# STM32_CORE.net
KiCad netlist of a schematic drawn in Altium Designer
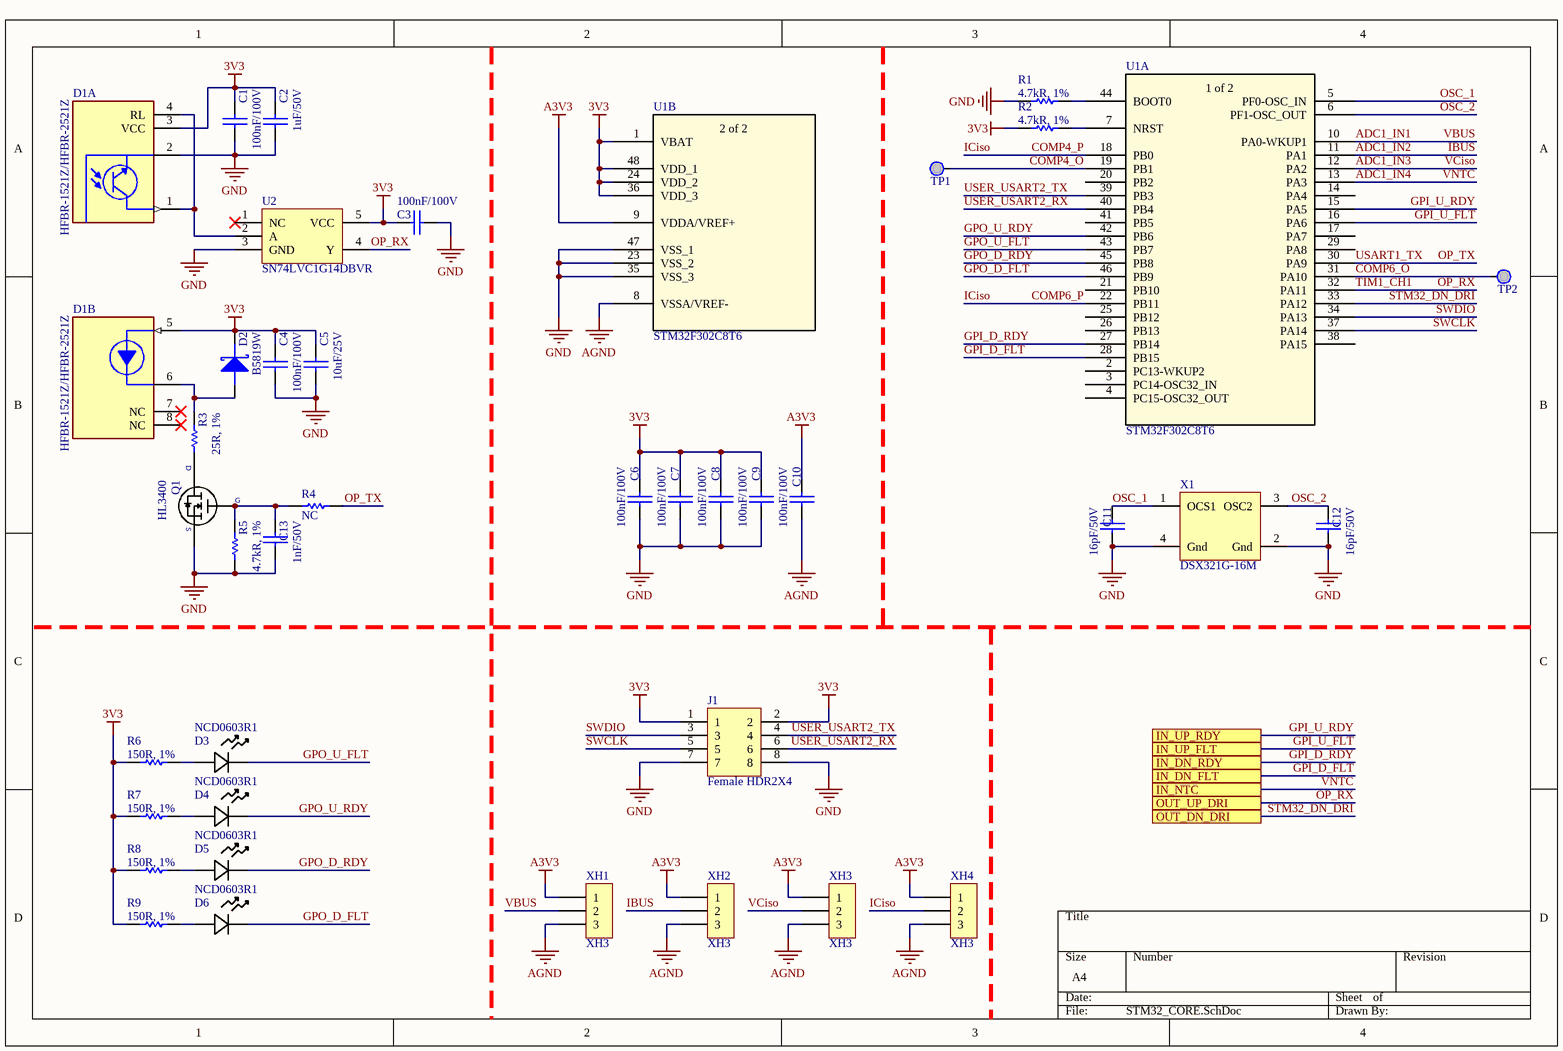
[diagram p0: STM32_CORE.SchDoc]

(export (version "E")
  (design (tool "Eeschema 10.0.6"))
  (components
    (comp (ref "C1")
      (value "100nF/100V")
      (footprint "0603C")
      (description "CC0603KRX7R9BB104")
      (libsource (lib "MyLib") (part "CAP"))
    )
    (comp (ref "C2")
      (value "1uF/50V")
      (footprint "0603C")
      (description "CC0603KRX7R9BB105")
      (libsource (lib "MyLib") (part "CAP"))
    )
    (comp (ref "C3")
      (value "100nF/100V")
      (footprint "0603C")
      (description "CC0603KRX7R9BB104")
      (libsource (lib "MyLib") (part "CAP"))
    )
    (comp (ref "C4")
      (value "100nF/100V")
      (footprint "0603C")
      (description "CC0603KRX7R9BB104")
      (libsource (lib "MyLib") (part "CAP"))
    )
    (comp (ref "C5")
      (value "10uF/25V")
      (footprint "0603C")
      (description "CC0603MRX5R8BB106")
      (libsource (lib "MyLib") (part "CAP"))
    )
    (comp (ref "C6")
      (value "100nF/100V")
      (footprint "0603C")
      (description "CC0603KRX7R9BB104")
      (libsource (lib "MyLib") (part "CAP"))
    )
    (comp (ref "C7")
      (value "100nF/100V")
      (footprint "0603C")
      (description "CC0603KRX7R9BB104")
      (libsource (lib "MyLib") (part "CAP"))
    )
    (comp (ref "C8")
      (value "100nF/100V")
      (footprint "0603C")
      (description "CC0603KRX7R9BB104")
      (libsource (lib "MyLib") (part "CAP"))
    )
    (comp (ref "C9")
      (value "100nF/100V")
      (footprint "0603C")
      (description "CC0603KRX7R9BB104")
      (libsource (lib "MyLib") (part "CAP"))
    )
    (comp (ref "C10")
      (value "100nF/100V")
      (footprint "0603C")
      (description "CC0603KRX7R9BB104")
      (libsource (lib "MyLib") (part "CAP"))
    )
    (comp (ref "C11")
      (value "16pF/50V")
      (footprint "0603C")
      (description "CC0603FRNPO9BN160")
      (libsource (lib "MyLib") (part "CAP"))
    )
    (comp (ref "C12")
      (value "16pF/50V")
      (footprint "0603C")
      (description "CC0603FRNPO9BN160")
      (libsource (lib "MyLib") (part "CAP"))
    )
    (comp (ref "C13")
      (value "1nF/50V")
      (footprint "0603C")
      (description "CC0603KRX7R9BB102")
      (libsource (lib "MyLib") (part "CAP"))
    )
    (comp (ref "D1")
      (value "HFBR-1521Z/HFBR-2521Z")
      (footprint "HFBR_XX21Z_UNION")
      (description "Versatile Link Fiber-Optic Connection")
      (libsource (lib "CustomizedLib") (part "HFBR_XX21Z_UNION"))
    )
    (comp (ref "D2") (value "B5819W") (footprint "SOD-123") (libsource (lib "MyLib") (part "DIODE SCHOTTKY")))
    (comp (ref "D3")
      (value "NCD0603R1")
      (footprint "LED_LSQ976_OSR")
      (description "No Description Available")
      (fields
        (field (name "MANUFACTURER_PART_NUMBER") "LSQ976")
        (field (name "COPYRIGHT") "Copyright (C) 2025 Ultra Librarian. All rights reserved.")
      )
      (libsource (lib "CustomizedLib") (part "LED"))
    )
    (comp (ref "D4")
      (value "NCD0603R1")
      (footprint "LED_LSQ976_OSR")
      (description "No Description Available")
      (fields
        (field (name "MANUFACTURER_PART_NUMBER") "LSQ976")
        (field (name "COPYRIGHT") "Copyright (C) 2025 Ultra Librarian. All rights reserved.")
      )
      (libsource (lib "CustomizedLib") (part "LED"))
    )
    (comp (ref "D5")
      (value "NCD0603R1")
      (footprint "LED_LSQ976_OSR")
      (description "No Description Available")
      (fields
        (field (name "MANUFACTURER_PART_NUMBER") "LSQ976")
        (field (name "COPYRIGHT") "Copyright (C) 2025 Ultra Librarian. All rights reserved.")
      )
      (libsource (lib "CustomizedLib") (part "LED"))
    )
    (comp (ref "D6")
      (value "NCD0603R1")
      (footprint "LED_LSQ976_OSR")
      (description "No Description Available")
      (fields
        (field (name "MANUFACTURER_PART_NUMBER") "LSQ976")
        (field (name "COPYRIGHT") "Copyright (C) 2025 Ultra Librarian. All rights reserved.")
      )
      (libsource (lib "CustomizedLib") (part "LED"))
    )
    (comp (ref "J1")
      (value "Female HDR2X4")
      (footprint "Fe-HDR2X4/2.54-S")
      (libsource (lib "MyLib") (part "Female HDR2X4"))
    )
    (comp (ref "Q1") (value "HL3400") (footprint "SOT23-3") (libsource (lib "CustomizedLib") (part "NMOS")))
    (comp (ref "R1")
      (value "4.7kR, 1%")
      (footprint "0603R")
      (description "RC0603FR-074K7L")
      (libsource (lib "MyLib") (part "RES"))
    )
    (comp (ref "R2")
      (value "4.7kR, 1%")
      (footprint "0603R")
      (description "RC0603FR-074K7L")
      (libsource (lib "MyLib") (part "RES"))
    )
    (comp (ref "R3")
      (value "25R, 1%")
      (footprint "0603R")
      (description "RP0603BRD0725RL")
      (libsource (lib "MyLib") (part "RES"))
    )
    (comp (ref "R4") (value "NC") (footprint "0603R") (libsource (lib "MyLib") (part "RES")))
    (comp (ref "R5")
      (value "4.7kR, 1%")
      (footprint "0603R")
      (description "RC0603FR-074K7L")
      (libsource (lib "MyLib") (part "RES"))
    )
    (comp (ref "R6")
      (value "150R, 1%")
      (footprint "0603R")
      (description "RC0603FR-07150RL")
      (libsource (lib "MyLib") (part "RES"))
    )
    (comp (ref "R7")
      (value "150R, 1%")
      (footprint "0603R")
      (description "RC0603FR-07150RL")
      (libsource (lib "MyLib") (part "RES"))
    )
    (comp (ref "R8")
      (value "150R, 1%")
      (footprint "0603R")
      (description "RC0603FR-07150RL")
      (libsource (lib "MyLib") (part "RES"))
    )
    (comp (ref "R9")
      (value "150R, 1%")
      (footprint "0603R")
      (description "RC0603FR-07150RL")
      (libsource (lib "MyLib") (part "RES"))
    )
    (comp (ref "TP1") (value "Test Point") (footprint "TP") (libsource (lib "CustomizedLib") (part "TP")))
    (comp (ref "TP2") (value "Test Point") (footprint "TP") (libsource (lib "CustomizedLib") (part "TP")))
    (comp (ref "U1")
      (value "STM32F302C8T6")
      (footprint "LQFP48-7x7mm")
      (fields (field (name "COPYRIGHT") "Copyright (C) 2025 Ultra Librarian. All rights reserved."))
      (libsource (lib "CustomizedLib") (part "STM32F302C8T6"))
    )
    (comp (ref "U2")
      (value "SN74LVC1G14DBVR")
      (footprint "SOT23-5")
      (description "Y=A\\")
      (libsource (lib "CustomizedLib") (part "SN74LVC1G14DBVR"))
    )
    (comp (ref "X1")
      (value "DSX321G-16M")
      (footprint "SMD3225-4")
      (description "无源晶振")
      (libsource (lib "CustomizedLib") (part "DSX321G-16M"))
    )
    (comp (ref "XH1") (value "XH3") (footprint "XH3/2.54mm/180") (libsource (lib "MyLib") (part "XH3")))
    (comp (ref "XH2") (value "XH3") (footprint "XH3/2.54mm/180") (libsource (lib "MyLib") (part "XH3")))
    (comp (ref "XH3") (value "XH3") (footprint "XH3/2.54mm/180") (libsource (lib "MyLib") (part "XH3")))
    (comp (ref "XH4") (value "XH3") (footprint "XH3/2.54mm/180") (libsource (lib "MyLib") (part "XH3")))
  )
  (nets
    (net (code "1") (name "/ADC1_IN1") (class "Default")
      (node (ref "U1") (pin "10") (pinfunction "PA0-WKUP1_10") (pintype "passive"))
      (node (ref "XH1") (pin "2") (pinfunction "2_2") (pintype "passive"))
    )
    (net (code "2") (name "/ADC1_IN2") (class "Default")
      (node (ref "U1") (pin "11") (pinfunction "PA1_11") (pintype "passive"))
      (node (ref "XH2") (pin "2") (pinfunction "2_2") (pintype "passive"))
    )
    (net (code "3") (name "/ADC1_IN3") (class "Default")
      (node (ref "U1") (pin "12") (pinfunction "PA2_12") (pintype "passive"))
      (node (ref "XH3") (pin "2") (pinfunction "2_2") (pintype "passive"))
    )
    (net (code "4") (name "/ADC1_IN4") (class "Default")
      (node (ref "U1") (pin "13") (pinfunction "PA3_13") (pintype "passive"))
    )
    (net (code "5") (name "/COMP4_O") (class "Default")
      (node (ref "TP1") (pin "1") (pinfunction "1_1") (pintype "passive"))
      (node (ref "U1") (pin "19") (pinfunction "PB1_19") (pintype "passive"))
    )
    (net (code "6") (name "/COMP4_P") (class "Default")
      (node (ref "U1") (pin "18") (pinfunction "PB0_18") (pintype "passive"))
      (node (ref "U1") (pin "22") (pinfunction "PB11_22") (pintype "passive"))
      (node (ref "XH4") (pin "2") (pinfunction "2_2") (pintype "passive"))
    )
    (net (code "7") (name "/COMP6_O") (class "Default")
      (node (ref "TP2") (pin "1") (pinfunction "1_1") (pintype "passive"))
      (node (ref "U1") (pin "31") (pinfunction "PA10_31") (pintype "passive"))
    )
    (net (code "8") (name "/GPI_D_FLT") (class "Default")
      (node (ref "U1") (pin "28") (pinfunction "PB15_28") (pintype "passive"))
    )
    (net (code "9") (name "/GPI_D_RDY") (class "Default")
      (node (ref "U1") (pin "27") (pinfunction "PB14_27") (pintype "passive"))
    )
    (net (code "10") (name "/GPI_U_FLT") (class "Default")
      (node (ref "U1") (pin "16") (pinfunction "PA6_16") (pintype "passive"))
    )
    (net (code "11") (name "/GPI_U_RDY") (class "Default")
      (node (ref "U1") (pin "15") (pinfunction "PA5_15") (pintype "passive"))
    )
    (net (code "12") (name "/GPO_D_FLT") (class "Default")
      (node (ref "D6") (pin "1") (pinfunction "1_1") (pintype "passive"))
      (node (ref "U1") (pin "46") (pinfunction "PB9_46") (pintype "passive"))
    )
    (net (code "13") (name "/GPO_D_RDY") (class "Default")
      (node (ref "D5") (pin "1") (pinfunction "1_1") (pintype "passive"))
      (node (ref "U1") (pin "45") (pinfunction "PB8_45") (pintype "passive"))
    )
    (net (code "14") (name "/GPO_U_FLT") (class "Default")
      (node (ref "D3") (pin "1") (pinfunction "1_1") (pintype "passive"))
      (node (ref "U1") (pin "43") (pinfunction "PB7_43") (pintype "passive"))
    )
    (net (code "15") (name "/GPO_U_RDY") (class "Default")
      (node (ref "D4") (pin "1") (pinfunction "1_1") (pintype "passive"))
      (node (ref "U1") (pin "42") (pinfunction "PB6_42") (pintype "passive"))
    )
    (net (code "16") (name "/OP_RX") (class "Default")
      (node (ref "U1") (pin "32") (pinfunction "PA11_32") (pintype "passive"))
      (node (ref "U2") (pin "4") (pinfunction "Y_4") (pintype "passive"))
    )
    (net (code "17") (name "/OP_TX") (class "Default")
      (node (ref "R4") (pin "1") (pinfunction "1_1") (pintype "passive"))
      (node (ref "U1") (pin "30") (pinfunction "PA9_30") (pintype "passive"))
    )
    (net (code "18") (name "/OSC_1") (class "Default")
      (node (ref "C11") (pin "2") (pinfunction "2_2") (pintype "passive"))
      (node (ref "U1") (pin "5") (pinfunction "PF0-OSC_IN_5") (pintype "passive"))
      (node (ref "X1") (pin "1") (pinfunction "OCS1_1") (pintype "passive"))
    )
    (net (code "19") (name "/OSC_2") (class "Default")
      (node (ref "C12") (pin "1") (pinfunction "1_1") (pintype "passive"))
      (node (ref "U1") (pin "6") (pinfunction "PF1-OSC_OUT_6") (pintype "passive"))
      (node (ref "X1") (pin "3") (pinfunction "OSC2_3") (pintype "passive"))
    )
    (net (code "20") (name "/STM32_DN_DRI") (class "Default")
      (node (ref "U1") (pin "33") (pinfunction "PA12_33") (pintype "passive"))
    )
    (net (code "21") (name "/SWCLK") (class "Default")
      (node (ref "J1") (pin "5") (pinfunction "5_5") (pintype "passive"))
      (node (ref "U1") (pin "37") (pinfunction "PA14_37") (pintype "passive"))
    )
    (net (code "22") (name "/SWDIO") (class "Default")
      (node (ref "J1") (pin "3") (pinfunction "3_3") (pintype "passive"))
      (node (ref "U1") (pin "34") (pinfunction "PA13_34") (pintype "passive"))
    )
    (net (code "23") (name "/USER_USART2_RX") (class "Default")
      (node (ref "J1") (pin "6") (pinfunction "6_6") (pintype "passive"))
      (node (ref "U1") (pin "40") (pinfunction "PB4_40") (pintype "passive"))
    )
    (net (code "24") (name "/USER_USART2_TX") (class "Default")
      (node (ref "J1") (pin "4") (pinfunction "4_4") (pintype "passive"))
      (node (ref "U1") (pin "39") (pinfunction "PB3_39") (pintype "passive"))
    )
    (net (code "25") (name "3V3") (class "Default")
      (node (ref "C1") (pin "1") (pinfunction "1_1") (pintype "passive"))
      (node (ref "C2") (pin "2") (pinfunction "2_2") (pintype "passive"))
      (node (ref "C3") (pin "1") (pinfunction "1_1") (pintype "passive"))
      (node (ref "C4") (pin "1") (pinfunction "1_1") (pintype "passive"))
      (node (ref "C5") (pin "1") (pinfunction "1_1") (pintype "passive"))
      (node (ref "C6") (pin "1") (pinfunction "1_1") (pintype "passive"))
      (node (ref "C7") (pin "1") (pinfunction "1_1") (pintype "passive"))
      (node (ref "C8") (pin "1") (pinfunction "1_1") (pintype "passive"))
      (node (ref "C9") (pin "1") (pinfunction "1_1") (pintype "passive"))
      (node (ref "D1") (pin "3") (pinfunction "VCC_3") (pintype "power_in"))
      (node (ref "D1") (pin "5") (pinfunction "VO_5") (pintype "input"))
      (node (ref "D2") (pin "K") (pinfunction "K_K") (pintype "passive"))
      (node (ref "J1") (pin "1") (pinfunction "1_1") (pintype "passive"))
      (node (ref "J1") (pin "2") (pinfunction "2_2") (pintype "passive"))
      (node (ref "R2") (pin "1") (pinfunction "1_1") (pintype "passive"))
      (node (ref "R6") (pin "1") (pinfunction "1_1") (pintype "passive"))
      (node (ref "R7") (pin "1") (pinfunction "1_1") (pintype "passive"))
      (node (ref "R8") (pin "1") (pinfunction "1_1") (pintype "passive"))
      (node (ref "R9") (pin "1") (pinfunction "1_1") (pintype "passive"))
      (node (ref "U1") (pin "1") (pinfunction "VBAT_1") (pintype "power_in"))
      (node (ref "U1") (pin "24") (pinfunction "VDD_2_24") (pintype "power_in"))
      (node (ref "U1") (pin "36") (pinfunction "VDD_3_36") (pintype "power_in"))
      (node (ref "U1") (pin "48") (pinfunction "VDD_1_48") (pintype "power_in"))
      (node (ref "U2") (pin "5") (pinfunction "VCC_5") (pintype "passive"))
    )
    (net (code "26") (name "A3V3") (class "Default")
      (node (ref "C10") (pin "1") (pinfunction "1_1") (pintype "passive"))
      (node (ref "U1") (pin "9") (pinfunction "VDDA/VREF+_9") (pintype "power_in"))
      (node (ref "XH1") (pin "1") (pinfunction "1_1") (pintype "passive"))
      (node (ref "XH2") (pin "1") (pinfunction "1_1") (pintype "passive"))
      (node (ref "XH3") (pin "1") (pinfunction "1_1") (pintype "passive"))
      (node (ref "XH4") (pin "1") (pinfunction "1_1") (pintype "passive"))
    )
    (net (code "27") (name "AGND") (class "Default")
      (node (ref "C10") (pin "2") (pinfunction "2_2") (pintype "passive"))
      (node (ref "U1") (pin "8") (pinfunction "VSSA/VREF-_8") (pintype "power_in"))
      (node (ref "XH1") (pin "3") (pinfunction "3_3") (pintype "passive"))
      (node (ref "XH2") (pin "3") (pinfunction "3_3") (pintype "passive"))
      (node (ref "XH3") (pin "3") (pinfunction "3_3") (pintype "passive"))
      (node (ref "XH4") (pin "3") (pinfunction "3_3") (pintype "passive"))
    )
    (net (code "28") (name "GND") (class "Default")
      (node (ref "C1") (pin "2") (pinfunction "2_2") (pintype "passive"))
      (node (ref "C11") (pin "1") (pinfunction "1_1") (pintype "passive"))
      (node (ref "C12") (pin "2") (pinfunction "2_2") (pintype "passive"))
      (node (ref "C13") (pin "1") (pinfunction "1_1") (pintype "passive"))
      (node (ref "C2") (pin "1") (pinfunction "1_1") (pintype "passive"))
      (node (ref "C3") (pin "2") (pinfunction "2_2") (pintype "passive"))
      (node (ref "C4") (pin "2") (pinfunction "2_2") (pintype "passive"))
      (node (ref "C5") (pin "2") (pinfunction "2_2") (pintype "passive"))
      (node (ref "C6") (pin "2") (pinfunction "2_2") (pintype "passive"))
      (node (ref "C7") (pin "2") (pinfunction "2_2") (pintype "passive"))
      (node (ref "C8") (pin "2") (pinfunction "2_2") (pintype "passive"))
      (node (ref "C9") (pin "2") (pinfunction "2_2") (pintype "passive"))
      (node (ref "D1") (pin "2") (pinfunction "GROUND_2") (pintype "power_in"))
      (node (ref "J1") (pin "7") (pinfunction "7_7") (pintype "passive"))
      (node (ref "J1") (pin "8") (pinfunction "8_8") (pintype "passive"))
      (node (ref "Q1") (pin "2") (pinfunction "2_2") (pintype "passive"))
      (node (ref "R1") (pin "1") (pinfunction "1_1") (pintype "passive"))
      (node (ref "R5") (pin "1") (pinfunction "1_1") (pintype "passive"))
      (node (ref "U1") (pin "23") (pinfunction "VSS_2_23") (pintype "power_in"))
      (node (ref "U1") (pin "35") (pinfunction "VSS_3_35") (pintype "power_in"))
      (node (ref "U1") (pin "47") (pinfunction "VSS_1_47") (pintype "power_in"))
      (node (ref "U2") (pin "3") (pinfunction "GND_3") (pintype "passive"))
      (node (ref "X1") (pin "2") (pinfunction "Gnd_2") (pintype "passive"))
      (node (ref "X1") (pin "4") (pinfunction "Gnd_4") (pintype "passive"))
    )
    (net (code "29") (name "Net-(C13-Pad2)") (class "Default")
      (node (ref "C13") (pin "2") (pinfunction "2_2") (pintype "passive"))
      (node (ref "Q1") (pin "1") (pinfunction "1_1") (pintype "passive"))
      (node (ref "R4") (pin "2") (pinfunction "2_2") (pintype "passive"))
      (node (ref "R5") (pin "2") (pinfunction "2_2") (pintype "passive"))
    )
    (net (code "30") (name "Net-(D1A-RL)") (class "Default")
      (node (ref "D1") (pin "1") (pinfunction "VO_1") (pintype "output"))
      (node (ref "D1") (pin "4") (pinfunction "RL_4") (pintype "passive"))
      (node (ref "U2") (pin "2") (pinfunction "A_2") (pintype "passive"))
    )
    (net (code "31") (name "Net-(D1B-GROUND)") (class "Default")
      (node (ref "D1") (pin "6") (pinfunction "GROUND_6") (pintype "power_in"))
      (node (ref "D2") (pin "A") (pinfunction "A_A") (pintype "passive"))
      (node (ref "R3") (pin "1") (pinfunction "1_1") (pintype "passive"))
    )
    (net (code "32") (name "Net-(D3-Pad2)") (class "Default")
      (node (ref "D3") (pin "2") (pinfunction "2_2") (pintype "passive"))
      (node (ref "R6") (pin "2") (pinfunction "2_2") (pintype "passive"))
    )
    (net (code "33") (name "Net-(D4-Pad2)") (class "Default")
      (node (ref "D4") (pin "2") (pinfunction "2_2") (pintype "passive"))
      (node (ref "R7") (pin "2") (pinfunction "2_2") (pintype "passive"))
    )
    (net (code "34") (name "Net-(D5-Pad2)") (class "Default")
      (node (ref "D5") (pin "2") (pinfunction "2_2") (pintype "passive"))
      (node (ref "R8") (pin "2") (pinfunction "2_2") (pintype "passive"))
    )
    (net (code "35") (name "Net-(D6-Pad2)") (class "Default")
      (node (ref "D6") (pin "2") (pinfunction "2_2") (pintype "passive"))
      (node (ref "R9") (pin "2") (pinfunction "2_2") (pintype "passive"))
    )
    (net (code "36") (name "Net-(Q1-Pad3)") (class "Default")
      (node (ref "Q1") (pin "3") (pinfunction "3_3") (pintype "passive"))
      (node (ref "R3") (pin "2") (pinfunction "2_2") (pintype "passive"))
    )
    (net (code "37") (name "Net-(U1A-BOOT0)") (class "Default")
      (node (ref "R1") (pin "2") (pinfunction "2_2") (pintype "passive"))
      (node (ref "U1") (pin "44") (pinfunction "BOOT0_44") (pintype "passive"))
    )
    (net (code "38") (name "Net-(U1A-NRST)") (class "Default")
      (node (ref "R2") (pin "2") (pinfunction "2_2") (pintype "passive"))
      (node (ref "U1") (pin "7") (pinfunction "NRST_7") (pintype "passive"))
    )
    (net (code "39") (name "unconnected-(D1B-NC-Pad7)") (class "Default")
      (node (ref "D1") (pin "7") (pinfunction "NC_7") (pintype "passive+no_connect"))
    )
    (net (code "40") (name "unconnected-(D1B-NC-Pad8)") (class "Default")
      (node (ref "D1") (pin "8") (pinfunction "NC_8") (pintype "power_in+no_connect"))
    )
    (net (code "41") (name "unconnected-(U1A-PA4-Pad14)") (class "Default")
      (node (ref "U1") (pin "14") (pinfunction "PA4_14") (pintype "passive"))
    )
    (net (code "42") (name "unconnected-(U1A-PA7-Pad17)") (class "Default")
      (node (ref "U1") (pin "17") (pinfunction "PA7_17") (pintype "passive"))
    )
    (net (code "43") (name "unconnected-(U1A-PA8-Pad29)") (class "Default")
      (node (ref "U1") (pin "29") (pinfunction "PA8_29") (pintype "passive"))
    )
    (net (code "44") (name "unconnected-(U1A-PA15-Pad38)") (class "Default")
      (node (ref "U1") (pin "38") (pinfunction "PA15_38") (pintype "passive"))
    )
    (net (code "45") (name "unconnected-(U1A-PB2-Pad20)") (class "Default")
      (node (ref "U1") (pin "20") (pinfunction "PB2_20") (pintype "passive"))
    )
    (net (code "46") (name "unconnected-(U1A-PB5-Pad41)") (class "Default")
      (node (ref "U1") (pin "41") (pinfunction "PB5_41") (pintype "passive"))
    )
    (net (code "47") (name "unconnected-(U1A-PB10-Pad21)") (class "Default")
      (node (ref "U1") (pin "21") (pinfunction "PB10_21") (pintype "passive"))
    )
    (net (code "48") (name "unconnected-(U1A-PB12-Pad25)") (class "Default")
      (node (ref "U1") (pin "25") (pinfunction "PB12_25") (pintype "passive"))
    )
    (net (code "49") (name "unconnected-(U1A-PB13-Pad26)") (class "Default")
      (node (ref "U1") (pin "26") (pinfunction "PB13_26") (pintype "passive"))
    )
    (net (code "50") (name "unconnected-(U1A-PC13-WKUP2-Pad2)") (class "Default")
      (node (ref "U1") (pin "2") (pinfunction "PC13-WKUP2_2") (pintype "passive"))
    )
    (net (code "51") (name "unconnected-(U1A-PC14-OSC32_IN-Pad3)") (class "Default")
      (node (ref "U1") (pin "3") (pinfunction "PC14-OSC32_IN_3") (pintype "passive"))
    )
    (net (code "52") (name "unconnected-(U1A-PC15-OSC32_OUT-Pad4)") (class "Default")
      (node (ref "U1") (pin "4") (pinfunction "PC15-OSC32_OUT_4") (pintype "passive"))
    )
    (net (code "53") (name "unconnected-(U2-NC-Pad1)") (class "Default")
      (node (ref "U2") (pin "1") (pinfunction "NC_1") (pintype "passive+no_connect"))
    )
  )
)
